# SCH_rocket-launcher_2024-12-23.net
KiCad netlist of a schematic drawn in EasyEDA
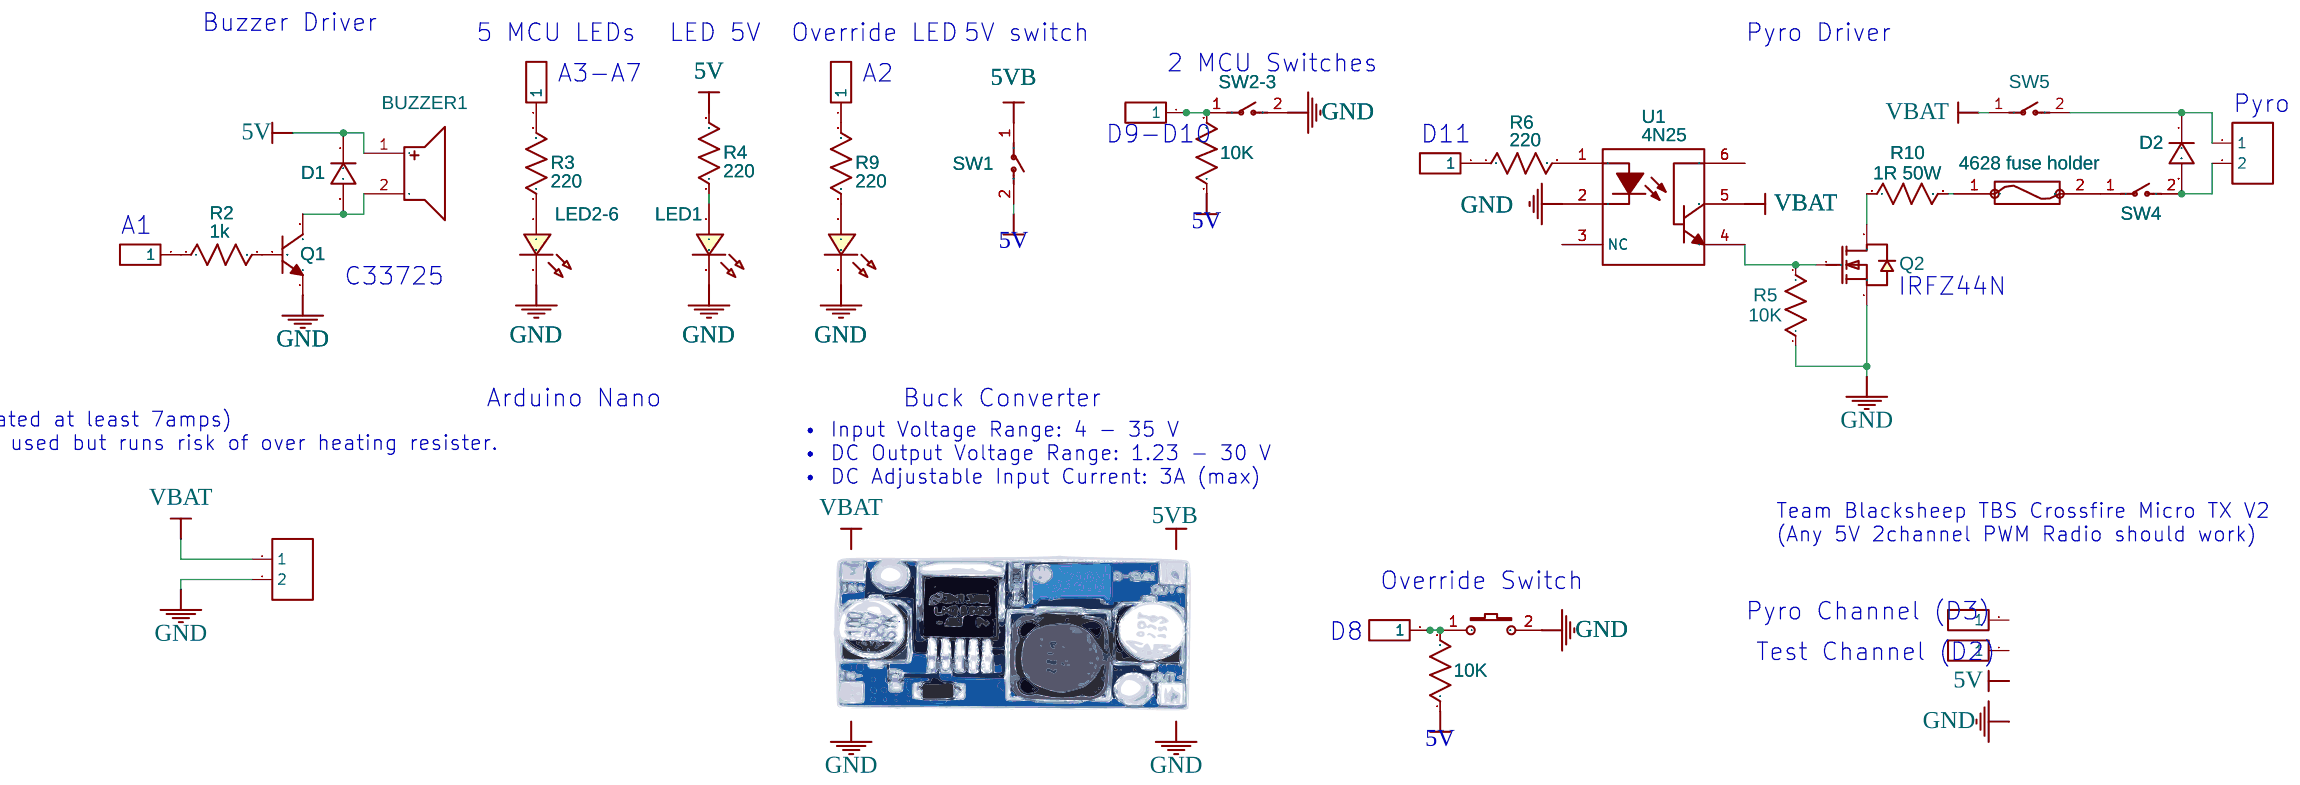
[diagram p0: schematic sheet]

(export (version "E")
  (design (tool "Eeschema 10.0.6"))
  (components
    (comp (ref "BUZZER1")
      (value "HND-13065B")
      (fields (field (name "Manufacturer") "华能"))
      (libsource (lib "") (part "HND-13065B"))
    )
    (comp (ref "D1")
      (value "1N4007W")
      (fields (field (name "Manufacturer") "BLUE ROCKET"))
      (libsource (lib "") (part "1N4007W"))
    )
    (comp (ref "D2")
      (value "1N4007W")
      (fields (field (name "Manufacturer") "BLUE ROCKET"))
      (libsource (lib "") (part "1N4007W"))
    )
    (comp (ref "J1") (value "HDR-M-2.54_1x1") (libsource (lib "") (part "HDR-M-2.54_1x1")))
    (comp (ref "J2-1") (value "HDR-M-2.54_1x1") (libsource (lib "") (part "HDR-M-2.54_1x1_1")))
    (comp (ref "J2-6") (value "HDR-M-2.54_1x1") (libsource (lib "") (part "HDR-M-2.54_1x1_1")))
    (comp (ref "J7-1") (value "HDR-M-2.54_1x1") (libsource (lib "") (part "HDR-M-2.54_1x1_2")))
    (comp (ref "J7-8") (value "HDR-M-2.54_1x1") (libsource (lib "") (part "HDR-M-2.54_1x1_2")))
    (comp (ref "J9") (value "HDR-M-2.54_1x1") (libsource (lib "") (part "HDR-M-2.54_1x1")))
    (comp (ref "J10") (value "HDR-M-2.54_1x1") (libsource (lib "") (part "HDR-M-2.54_1x1")))
    (comp (ref "KEY1")
      (value "K2-3.6×6.1_SMD")
      (fields (field (name "Manufacturer Part") "K2-1107ST-A4SW-06"))
      (libsource (lib "") (part "K2-3.6×6.1_SMD"))
    )
    (comp (ref "LED1")
      (value "LED-0603_R")
      (fields
        (field (name "Manufacturer Part") "19-217/R6C-AL1M2VY/3T")
        (field (name "Manufacturer") "EVERLIGHT(台湾亿光)")
      )
      (libsource (lib "") (part "LED-0603_R"))
    )
    (comp (ref "LED2-1")
      (value "LED-0603_R")
      (fields
        (field (name "Manufacturer Part") "19-217/R6C-AL1M2VY/3T")
        (field (name "Manufacturer") "EVERLIGHT(台湾亿光)")
      )
      (libsource (lib "") (part "LED-0603_R_1"))
    )
    (comp (ref "LED2-6")
      (value "LED-0603_R")
      (fields
        (field (name "Manufacturer Part") "19-217/R6C-AL1M2VY/3T")
        (field (name "Manufacturer") "EVERLIGHT(台湾亿光)")
      )
      (libsource (lib "") (part "LED-0603_R_1"))
    )
    (comp (ref "P1") (value "CONN-TH_2P-P5.00") (libsource (lib "") (part "CONN-TH_2P-P5.00")))
    (comp (ref "P2") (value "CONN-TH_2P-P5.00") (libsource (lib "") (part "CONN-TH_2P-P5.00")))
    (comp (ref "Q1")
      (value "2N3904(SOT-23)")
      (fields (field (name "Manufacturer Part") "2n3904S-RTK/PS") (field (name "Manufacturer") "KEC"))
      (libsource (lib "") (part "2N3904(SOT-23)"))
    )
    (comp (ref "Q2")
      (value "2N7002")
      (fields (field (name "Manufacturer Part") "2N7002,215") (field (name "Manufacturer") "Nexperia"))
      (libsource (lib "") (part "2N7002"))
    )
    (comp (ref "R2") (value "1k") (libsource (lib "") (part "R_0603_US_1")))
    (comp (ref "R3") (value "220") (libsource (lib "") (part "R_0603_US")))
    (comp (ref "R4") (value "220") (libsource (lib "") (part "R_0603_US")))
    (comp (ref "R5") (value "10K") (libsource (lib "") (part "R_0603_US")))
    (comp (ref "R6") (value "220") (libsource (lib "") (part "R_0603_US_1")))
    (comp (ref "R7") (value "10K") (libsource (lib "") (part "R_0603_US")))
    (comp (ref "R8") (value "10K") (libsource (lib "") (part "R_0603_US")))
    (comp (ref "R9") (value "220") (libsource (lib "") (part "R_0603_US")))
    (comp (ref "R10") (value "1R 50W") (libsource (lib "") (part "R_0603_US_1")))
    (comp (ref "SW1")
      (value "KCD11-2P-R")
      (fields (field (name "Manufacturer") "SHOU HAN(首韩)"))
      (libsource (lib "") (part "KCD11-2P-R_2"))
    )
    (comp (ref "SW2-3")
      (value "KCD11-2P-R")
      (fields (field (name "Manufacturer") "SHOU HAN(首韩)"))
      (libsource (lib "") (part "KCD11-2P-R_1"))
    )
    (comp (ref "SW4")
      (value "KCD11-2P-R")
      (fields (field (name "Manufacturer") "SHOU HAN(首韩)"))
      (libsource (lib "") (part "KCD11-2P-R"))
    )
    (comp (ref "SW5")
      (value "KCD11-2P-R")
      (fields (field (name "Manufacturer") "SHOU HAN(首韩)"))
      (libsource (lib "") (part "KCD11-2P-R"))
    )
    (comp (ref "U1")
      (value "4N25")
      (fields (field (name "Manufacturer") "EVERLIGHT(亿光)"))
      (libsource (lib "") (part "4N25"))
    )
    (comp (ref "U2")
      (value "4628 fuse holder")
      (fields (field (name "Manufacturer Part") "4628C") (field (name "Manufacturer") "Keystone"))
      (libsource (lib "") (part "4628 fuse holder"))
    )
  )
  (nets
    (net (code "1") (name "5V") (class "Default")
      (node (ref "BUZZER1") (pin "1") (pinfunction "1_1") (pintype "unspecified"))
      (node (ref "D1") (pin "1") (pinfunction "1_1") (pintype "unspecified"))
      (node (ref "R4") (pin "2") (pinfunction "2_2") (pintype "unspecified"))
      (node (ref "R7") (pin "1") (pinfunction "1_1") (pintype "unspecified"))
      (node (ref "R8") (pin "1") (pinfunction "1_1") (pintype "unspecified"))
      (node (ref "SW1") (pin "2") (pinfunction "2_2") (pintype "unspecified"))
    )
    (net (code "2") (name "5VB") (class "Default")
      (node (ref "SW1") (pin "1") (pinfunction "1_1") (pintype "unspecified"))
    )
    (net (code "3") (name "GND") (class "Default")
      (node (ref "KEY1") (pin "2") (pinfunction "2_2") (pintype "unspecified"))
      (node (ref "LED1") (pin "2") (pinfunction "2_2") (pintype "unspecified"))
      (node (ref "LED2-1") (pin "2") (pinfunction "2_2") (pintype "unspecified"))
      (node (ref "LED2-6") (pin "2") (pinfunction "2_2") (pintype "unspecified"))
      (node (ref "P2") (pin "2") (pinfunction "2_2") (pintype "unspecified"))
      (node (ref "Q1") (pin "1") (pinfunction "E_1") (pintype "input"))
      (node (ref "Q2") (pin "2") (pinfunction "S_2") (pintype "unspecified"))
      (node (ref "R5") (pin "1") (pinfunction "1_1") (pintype "unspecified"))
      (node (ref "SW2-3") (pin "2") (pinfunction "2_2") (pintype "unspecified"))
      (node (ref "U1") (pin "2") (pinfunction "2_2") (pintype "unspecified"))
    )
    (net (code "4") (name "Net-(D2-Pad1)") (class "Default")
      (node (ref "D2") (pin "1") (pinfunction "1_1") (pintype "unspecified"))
      (node (ref "P1") (pin "1") (pinfunction "1_1") (pintype "unspecified"))
      (node (ref "SW5") (pin "2") (pinfunction "2_2") (pintype "unspecified"))
    )
    (net (code "5") (name "Net-(D2-Pad2)") (class "Default")
      (node (ref "D2") (pin "2") (pinfunction "2_2") (pintype "unspecified"))
      (node (ref "P1") (pin "2") (pinfunction "2_2") (pintype "unspecified"))
      (node (ref "SW4") (pin "2") (pinfunction "2_2") (pintype "unspecified"))
    )
    (net (code "6") (name "Net-(J1-Pad1)") (class "Default")
      (node (ref "J1") (pin "1") (pinfunction "1_1") (pintype "input"))
      (node (ref "R2") (pin "1") (pinfunction "1_1") (pintype "unspecified"))
    )
    (net (code "7") (name "Net-(J2-1-Pad1)") (class "Default")
      (node (ref "J2-1") (pin "1") (pinfunction "1_1") (pintype "input"))
      (node (ref "R9") (pin "2") (pinfunction "2_2") (pintype "unspecified"))
    )
    (net (code "8") (name "Net-(J2-6-Pad1)") (class "Default")
      (node (ref "J2-6") (pin "1") (pinfunction "1_1") (pintype "input"))
      (node (ref "R3") (pin "2") (pinfunction "2_2") (pintype "unspecified"))
    )
    (net (code "9") (name "Net-(J7-1-Pad1)") (class "Default")
      (node (ref "J7-1") (pin "1") (pinfunction "1_1") (pintype "input"))
      (node (ref "KEY1") (pin "1") (pinfunction "1_1") (pintype "unspecified"))
      (node (ref "R8") (pin "2") (pinfunction "2_2") (pintype "unspecified"))
    )
    (net (code "10") (name "Net-(J7-8-Pad1)") (class "Default")
      (node (ref "J7-8") (pin "1") (pinfunction "1_1") (pintype "input"))
      (node (ref "R7") (pin "2") (pinfunction "2_2") (pintype "unspecified"))
      (node (ref "SW2-3") (pin "1") (pinfunction "1_1") (pintype "unspecified"))
    )
    (net (code "11") (name "Net-(J9-Pad1)_1") (class "Default")
      (node (ref "J9") (pin "1") (pinfunction "1_1") (pintype "input"))
      (node (ref "R6") (pin "1") (pinfunction "1_1") (pintype "unspecified"))
    )
    (net (code "12") (name "Net-(LED1-Pad1)") (class "Default")
      (node (ref "LED1") (pin "1") (pinfunction "1_1") (pintype "unspecified"))
      (node (ref "R4") (pin "1") (pinfunction "1_1") (pintype "unspecified"))
    )
    (net (code "13") (name "Net-(LED2-1-Pad1)") (class "Default")
      (node (ref "LED2-1") (pin "1") (pinfunction "1_1") (pintype "unspecified"))
      (node (ref "R9") (pin "1") (pinfunction "1_1") (pintype "unspecified"))
    )
    (net (code "14") (name "Net-(LED2-6-Pad1)") (class "Default")
      (node (ref "LED2-6") (pin "1") (pinfunction "1_1") (pintype "unspecified"))
      (node (ref "R3") (pin "1") (pinfunction "1_1") (pintype "unspecified"))
    )
    (net (code "15") (name "Net-(Q1-B)") (class "Default")
      (node (ref "Q1") (pin "2") (pinfunction "B_2") (pintype "input"))
      (node (ref "R2") (pin "2") (pinfunction "2_2") (pintype "unspecified"))
    )
    (net (code "16") (name "Net-(Q1-C)") (class "Default")
      (node (ref "BUZZER1") (pin "2") (pinfunction "2_2") (pintype "unspecified"))
      (node (ref "D1") (pin "2") (pinfunction "2_2") (pintype "unspecified"))
      (node (ref "Q1") (pin "3") (pinfunction "C_3") (pintype "input"))
    )
    (net (code "17") (name "Net-(Q2-D)") (class "Default")
      (node (ref "Q2") (pin "3") (pinfunction "D_3") (pintype "unspecified"))
      (node (ref "R10") (pin "1") (pinfunction "1_1") (pintype "unspecified"))
    )
    (net (code "18") (name "Net-(Q2-G)") (class "Default")
      (node (ref "Q2") (pin "1") (pinfunction "G_1") (pintype "unspecified"))
      (node (ref "R5") (pin "2") (pinfunction "2_2") (pintype "unspecified"))
      (node (ref "U1") (pin "4") (pinfunction "4_4") (pintype "unspecified"))
    )
    (net (code "19") (name "Net-(R6-Pad2)") (class "Default")
      (node (ref "R6") (pin "2") (pinfunction "2_2") (pintype "unspecified"))
      (node (ref "U1") (pin "1") (pinfunction "1_1") (pintype "unspecified"))
    )
    (net (code "20") (name "Net-(R10-Pad2)") (class "Default")
      (node (ref "R10") (pin "2") (pinfunction "2_2") (pintype "unspecified"))
      (node (ref "U2") (pin "1") (pinfunction "1_1") (pintype "unspecified"))
    )
    (net (code "21") (name "Net-(SW4-Pad1)") (class "Default")
      (node (ref "SW4") (pin "1") (pinfunction "1_1") (pintype "unspecified"))
      (node (ref "U2") (pin "2") (pinfunction "2_2") (pintype "unspecified"))
    )
    (net (code "22") (name "VBAT") (class "Default")
      (node (ref "P2") (pin "1") (pinfunction "1_1") (pintype "unspecified"))
      (node (ref "SW5") (pin "1") (pinfunction "1_1") (pintype "unspecified"))
      (node (ref "U1") (pin "5") (pinfunction "5_5") (pintype "unspecified"))
    )
    (net (code "23") (name "unconnected-(J9-Pad1)") (class "Default")
      (node (ref "J9") (pin "1") (pinfunction "1_1") (pintype "input"))
    )
    (net (code "24") (name "unconnected-(J10-Pad1)") (class "Default")
      (node (ref "J10") (pin "1") (pinfunction "1_1") (pintype "input"))
    )
    (net (code "25") (name "unconnected-(U1-NC-Pad3)") (class "Default")
      (node (ref "U1") (pin "3") (pinfunction "NC_3") (pintype "unspecified"))
    )
    (net (code "26") (name "unconnected-(U1-Pad6)") (class "Default")
      (node (ref "U1") (pin "6") (pinfunction "6_6") (pintype "unspecified"))
    )
  )
)
